# WooferAmpIR2153.net
KiCad netlist of a schematic drawn in EAGLE
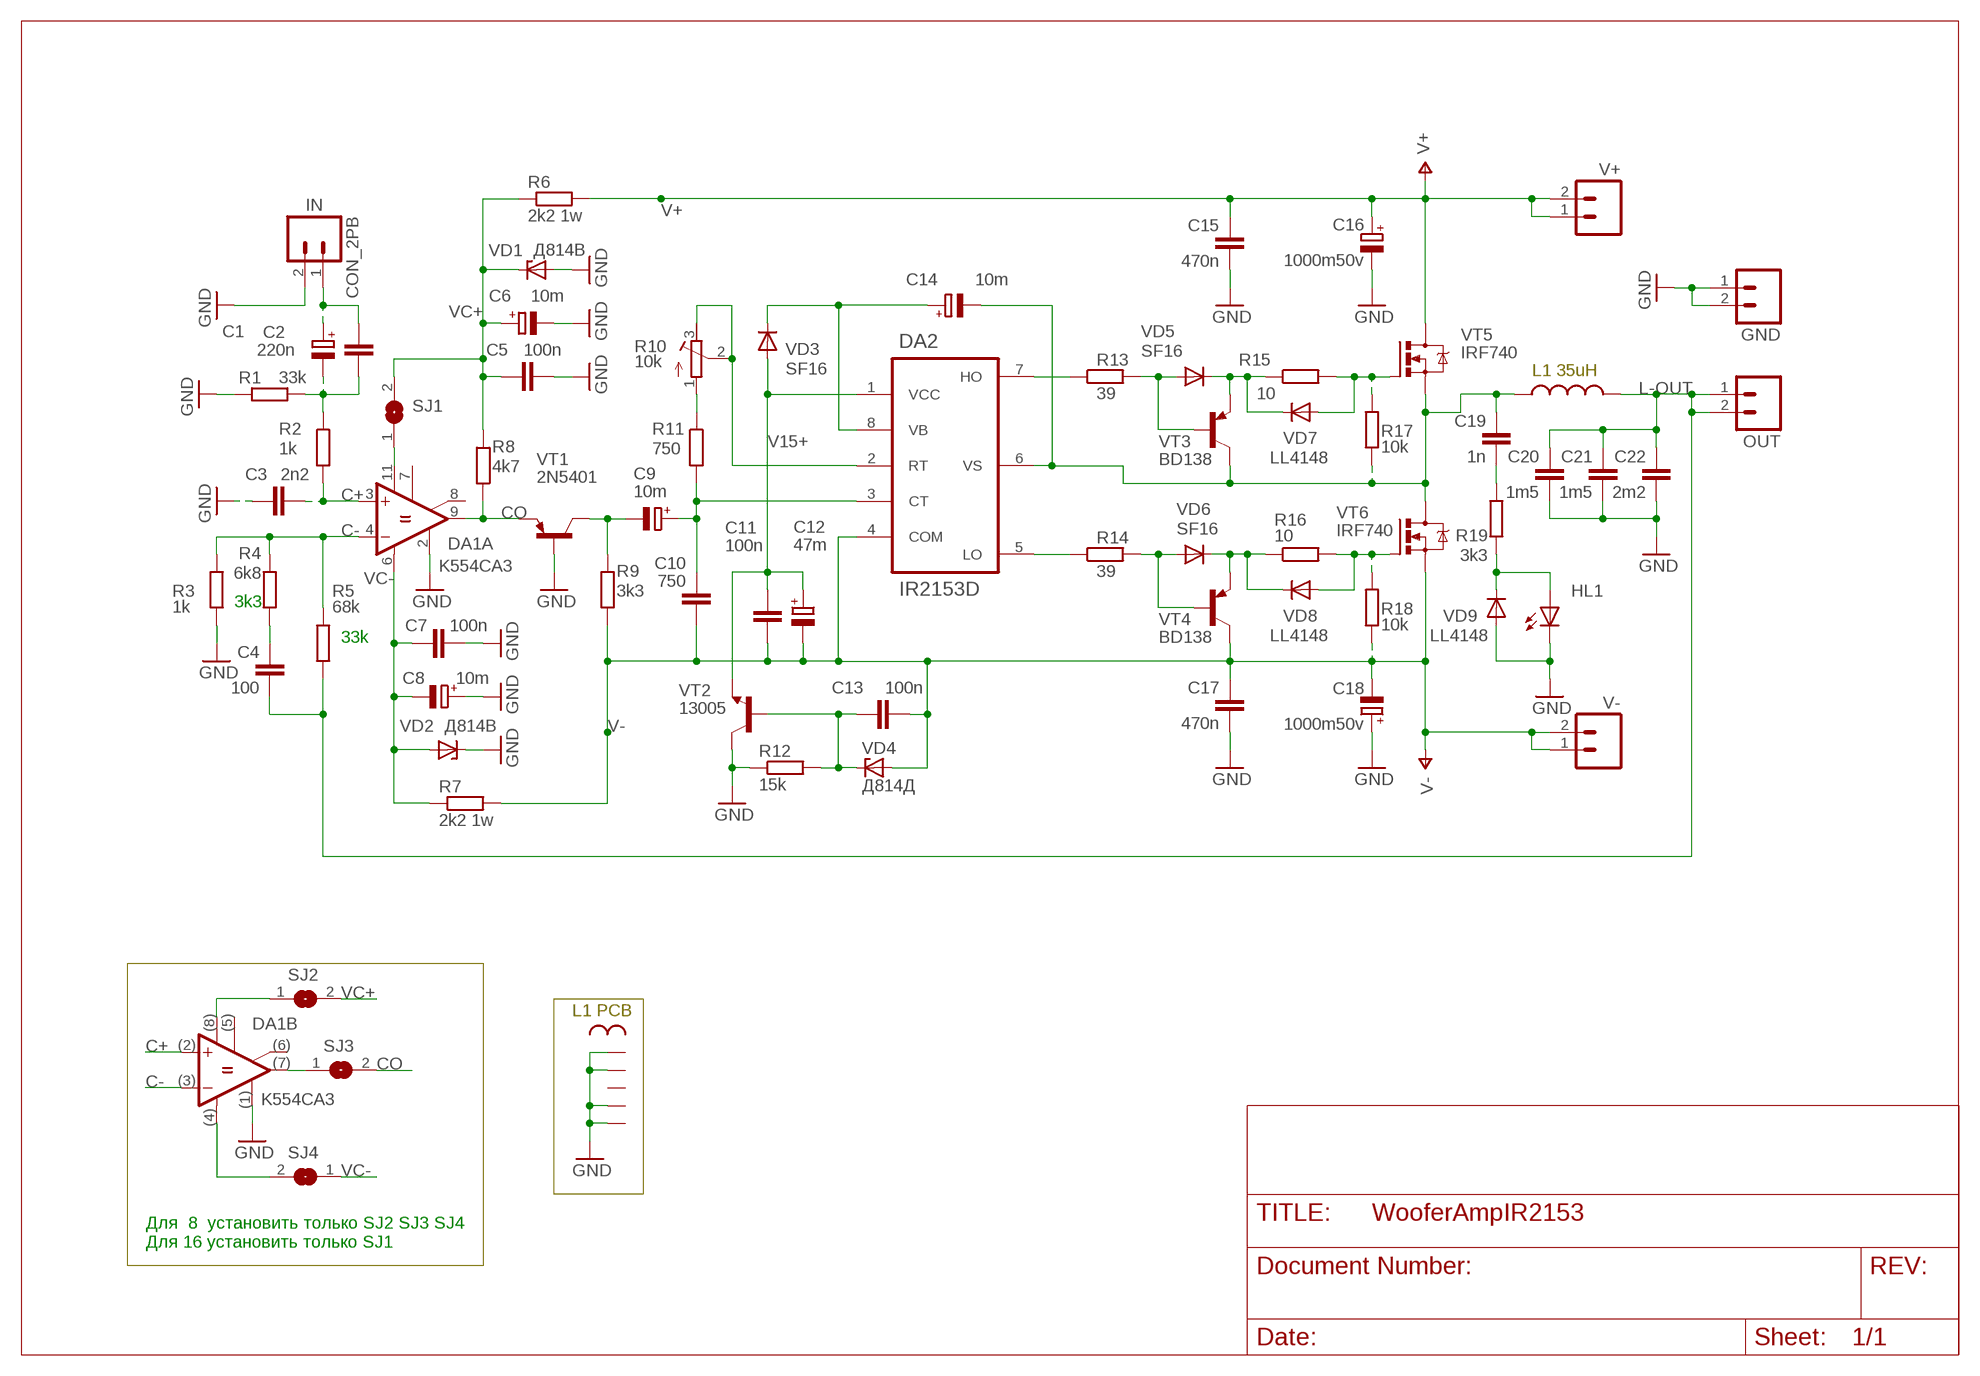
[diagram p0: schematic, sheet 1]

(export (version "E")
  (design (tool "Eeschema 10.0.6"))
  (components
    (comp (ref "C1")
      (value "CPOL-EUE2.5-6")
      (footprint "eagle-import:E2,5-6")
      (libsource (lib "eagle-import") (part "CPOL-EUE2.5-6"))
    )
    (comp (ref "C2")
      (value "220n")
      (footprint "eagle-import:C050-025X075")
      (libsource (lib "eagle-import") (part "C-EU050-025X075"))
    )
    (comp (ref "C3")
      (value "2n2")
      (footprint "eagle-import:C050-025X075")
      (libsource (lib "eagle-import") (part "C-EU050-025X075"))
    )
    (comp (ref "C4")
      (value "100")
      (footprint "eagle-import:C_11X3.5")
      (libsource (lib "eagle-import") (part "C11X3.5"))
    )
    (comp (ref "C5")
      (value "100n")
      (footprint "eagle-import:C075-032X103")
      (libsource (lib "eagle-import") (part "C-EU075-032X103"))
    )
    (comp (ref "C6")
      (value "10m")
      (footprint "eagle-import:E2,5-6")
      (libsource (lib "eagle-import") (part "CPOL-EUE2.5-6"))
    )
    (comp (ref "C7")
      (value "100n")
      (footprint "eagle-import:C050-025X075")
      (libsource (lib "eagle-import") (part "C-EU050-025X075"))
    )
    (comp (ref "C8")
      (value "10m")
      (footprint "eagle-import:E2,5-6")
      (libsource (lib "eagle-import") (part "CPOL-EUE2.5-6"))
    )
    (comp (ref "C9")
      (value "10m")
      (footprint "eagle-import:E2,5-6")
      (libsource (lib "eagle-import") (part "CPOL-EUE2.5-6"))
    )
    (comp (ref "C10")
      (value "750")
      (footprint "eagle-import:C075-032X103")
      (libsource (lib "eagle-import") (part "C-EU075-032X103"))
    )
    (comp (ref "C11")
      (value "100n")
      (footprint "eagle-import:C050-025X075")
      (libsource (lib "eagle-import") (part "C-EU050-025X075"))
    )
    (comp (ref "C12")
      (value "47m")
      (footprint "eagle-import:E2,5-6")
      (libsource (lib "eagle-import") (part "CPOL-EUE2.5-6"))
    )
    (comp (ref "C13")
      (value "100n")
      (footprint "eagle-import:C050-025X075")
      (libsource (lib "eagle-import") (part "C-EU050-025X075"))
    )
    (comp (ref "C14")
      (value "10m")
      (footprint "eagle-import:E2,5-6")
      (libsource (lib "eagle-import") (part "CPOL-EUE2.5-6"))
    )
    (comp (ref "C15")
      (value "470n")
      (footprint "eagle-import:C150-072X183")
      (libsource (lib "eagle-import") (part "C-EU150-072X183"))
    )
    (comp (ref "C16")
      (value "1000m50v")
      (footprint "eagle-import:E7,5-18")
      (libsource (lib "eagle-import") (part "CPOL-EUE7.5-18"))
    )
    (comp (ref "C17")
      (value "470n")
      (footprint "eagle-import:C150-072X183")
      (libsource (lib "eagle-import") (part "C-EU150-072X183"))
    )
    (comp (ref "C18")
      (value "1000m50v")
      (footprint "eagle-import:E7,5-18")
      (libsource (lib "eagle-import") (part "CPOL-EUE7.5-18"))
    )
    (comp (ref "C19")
      (value "1n")
      (footprint "eagle-import:C050-025X075")
      (libsource (lib "eagle-import") (part "C-EU050-025X075"))
    )
    (comp (ref "C20")
      (value "1m5")
      (footprint "eagle-import:C_22X13")
      (libsource (lib "eagle-import") (part "C22X13"))
    )
    (comp (ref "C21")
      (value "1m5")
      (footprint "eagle-import:C_22X13")
      (libsource (lib "eagle-import") (part "C22X13"))
    )
    (comp (ref "C22")
      (value "2m2")
      (footprint "eagle-import:C_23X16")
      (libsource (lib "eagle-import") (part "C23X16"))
    )
    (comp (ref "DA1")
      (value "K554CA3")
      (footprint "eagle-import:DIL_A(14)")
      (libsource (lib "eagle-import") (part "COMPMOD-K554CA3{dblquote}"))
    )
    (comp (ref "DA2")
      (value "IR2153D")
      (footprint "eagle-import:DIL8")
      (libsource (lib "eagle-import") (part "IR2153D"))
    )
    (comp (ref "GND")
      (value "CON_2PA")
      (footprint "eagle-import:CON_PWR_2PIN4MM")
      (libsource (lib "eagle-import") (part "CON_2PA"))
    )
    (comp (ref "HL1")
      (value "LED3MM")
      (footprint "eagle-import:LED3MM")
      (libsource (lib "eagle-import") (part "LED3MM"))
    )
    (comp (ref "IN")
      (value "CON_2PB")
      (footprint "eagle-import:CON_PWRI_2PIN4MM")
      (libsource (lib "eagle-import") (part "CON_2PB"))
    )
    (comp (ref "OUT")
      (value "CON_2PA")
      (footprint "eagle-import:CON_PWR_2PIN4MM")
      (libsource (lib "eagle-import") (part "CON_2PA"))
    )
    (comp (ref "R1")
      (value "33k")
      (footprint "eagle-import:0207_10")
      (libsource (lib "eagle-import") (part "R-EU_0207/10"))
    )
    (comp (ref "R2")
      (value "1k")
      (footprint "eagle-import:0207_10")
      (libsource (lib "eagle-import") (part "R-EU_0207/10"))
    )
    (comp (ref "R3")
      (value "1k")
      (footprint "eagle-import:M0805")
      (libsource (lib "eagle-import") (part "R-EU_M0805"))
    )
    (comp (ref "R4")
      (value "6k8")
      (footprint "eagle-import:M0805")
      (libsource (lib "eagle-import") (part "R-EU_M0805"))
    )
    (comp (ref "R5")
      (value "68k")
      (footprint "eagle-import:M1206")
      (libsource (lib "eagle-import") (part "R-EU_M1206"))
    )
    (comp (ref "R6")
      (value "2k2 1w")
      (footprint "eagle-import:P0613_15")
      (libsource (lib "eagle-import") (part "R-EU_0613/15"))
    )
    (comp (ref "R7")
      (value "2k2 1w")
      (footprint "eagle-import:P0613_15")
      (libsource (lib "eagle-import") (part "R-EU_0613/15"))
    )
    (comp (ref "R8")
      (value "4k7")
      (footprint "eagle-import:M0805")
      (libsource (lib "eagle-import") (part "R-EU_M0805"))
    )
    (comp (ref "R9")
      (value "3k3")
      (footprint "eagle-import:0207_10")
      (libsource (lib "eagle-import") (part "R-EU_0207/10"))
    )
    (comp (ref "R10")
      (value "10k")
      (footprint "eagle-import:RTRIM3296W")
      (libsource (lib "eagle-import") (part "R-TRIMM3296W"))
    )
    (comp (ref "R11")
      (value "750")
      (footprint "eagle-import:M0805")
      (libsource (lib "eagle-import") (part "R-EU_M0805"))
    )
    (comp (ref "R12")
      (value "15k")
      (footprint "eagle-import:0207_10")
      (libsource (lib "eagle-import") (part "R-EU_0207/10"))
    )
    (comp (ref "R13")
      (value "39")
      (footprint "eagle-import:M1206")
      (libsource (lib "eagle-import") (part "R-EU_M1206"))
    )
    (comp (ref "R14")
      (value "39")
      (footprint "eagle-import:M1206")
      (libsource (lib "eagle-import") (part "R-EU_M1206"))
    )
    (comp (ref "R15")
      (value "10")
      (footprint "eagle-import:M1206")
      (libsource (lib "eagle-import") (part "R-EU_M1206"))
    )
    (comp (ref "R16")
      (value "10")
      (footprint "eagle-import:M1206")
      (libsource (lib "eagle-import") (part "R-EU_M1206"))
    )
    (comp (ref "R17")
      (value "10k")
      (footprint "eagle-import:M1206")
      (libsource (lib "eagle-import") (part "R-EU_M1206"))
    )
    (comp (ref "R18")
      (value "10k")
      (footprint "eagle-import:M1206")
      (libsource (lib "eagle-import") (part "R-EU_M1206"))
    )
    (comp (ref "R19")
      (value "3k3")
      (footprint "eagle-import:M1206")
      (libsource (lib "eagle-import") (part "R-EU_M1206"))
    )
    (comp (ref "SJ1") (value "SJ") (footprint "eagle-import:SJ") (libsource (lib "eagle-import") (part "SJ")))
    (comp (ref "SJ2") (value "SJ") (footprint "eagle-import:SJ") (libsource (lib "eagle-import") (part "SJ")))
    (comp (ref "SJ3") (value "SJ") (footprint "eagle-import:SJ") (libsource (lib "eagle-import") (part "SJ")))
    (comp (ref "SJ4") (value "SJ") (footprint "eagle-import:SJ") (libsource (lib "eagle-import") (part "SJ")))
    (comp (ref "U$1")
      (value "L-D30")
      (footprint "eagle-import:L-D30")
      (libsource (lib "eagle-import") (part "L-D30"))
    )
    (comp (ref "U$4")
      (value "PIN")
      (footprint "eagle-import:PIN-L")
      (libsource (lib "eagle-import") (part "PIN"))
    )
    (comp (ref "U$11")
      (value "PIN")
      (footprint "eagle-import:PIN-L")
      (libsource (lib "eagle-import") (part "PIN"))
    )
    (comp (ref "V+")
      (value "CON_2PA")
      (footprint "eagle-import:CON_PWR_2PIN4MM")
      (libsource (lib "eagle-import") (part "CON_2PA"))
    )
    (comp (ref "V-")
      (value "CON_2PA")
      (footprint "eagle-import:CON_PWR_2PIN4MM")
      (libsource (lib "eagle-import") (part "CON_2PA"))
    )
    (comp (ref "VD1")
      (value "Д814В")
      (footprint "eagle-import:ZDMETAL")
      (libsource (lib "eagle-import") (part "ZDD814"))
    )
    (comp (ref "VD2")
      (value "Д814В")
      (footprint "eagle-import:ZDMETAL")
      (libsource (lib "eagle-import") (part "ZDD814"))
    )
    (comp (ref "VD3")
      (value "SF16")
      (footprint "eagle-import:DO204-10")
      (libsource (lib "eagle-import") (part "DIODE-DO204-10"))
    )
    (comp (ref "VD4")
      (value "Д814Д")
      (footprint "eagle-import:ZDMETAL")
      (libsource (lib "eagle-import") (part "ZDD814"))
    )
    (comp (ref "VD5")
      (value "SF16")
      (footprint "eagle-import:DO204-10")
      (libsource (lib "eagle-import") (part "DIODE-DO204-10"))
    )
    (comp (ref "VD6")
      (value "SF16")
      (footprint "eagle-import:DO204-10")
      (libsource (lib "eagle-import") (part "DIODE-DO204-10"))
    )
    (comp (ref "VD7")
      (value "LL4148")
      (footprint "eagle-import:SOD80C")
      (libsource (lib "eagle-import") (part "DIODE-SOD80C"))
    )
    (comp (ref "VD8")
      (value "LL4148")
      (footprint "eagle-import:SOD80C")
      (libsource (lib "eagle-import") (part "DIODE-SOD80C"))
    )
    (comp (ref "VD9")
      (value "LL4148")
      (footprint "eagle-import:SOD80C")
      (libsource (lib "eagle-import") (part "DIODE-SOD80C"))
    )
    (comp (ref "VT1")
      (value "2N5401")
      (footprint "eagle-import:TO92")
      (libsource (lib "eagle-import") (part "BJT_PNP_TO-92_EBC"))
    )
    (comp (ref "VT2")
      (value "13005")
      (footprint "eagle-import:TO220FV")
      (libsource (lib "eagle-import") (part "BJT_NPN_TO220_V_BCE"))
    )
    (comp (ref "VT3")
      (value "BD138")
      (footprint "eagle-import:TO126V")
      (libsource (lib "eagle-import") (part "BJT_PNP_TO126_V_ECB"))
    )
    (comp (ref "VT4")
      (value "BD138")
      (footprint "eagle-import:TO126V")
      (libsource (lib "eagle-import") (part "BJT_PNP_TO126_V_ECB"))
    )
    (comp (ref "VT5")
      (value "IRF740")
      (footprint "eagle-import:TO220")
      (libsource (lib "eagle-import") (part "IRF740"))
    )
    (comp (ref "VT6")
      (value "IRF740")
      (footprint "eagle-import:TO220")
      (libsource (lib "eagle-import") (part "IRF740"))
    )
  )
  (nets
    (net (code "1") (name "/C+") (class "Default")
      (node (ref "C3") (pin "2") (pinfunction "2_2") (pintype "passive"))
      (node (ref "DA1") (pin "(2)") (pinfunction "+IN_(2)") (pintype "input"))
      (node (ref "DA1") (pin "3") (pinfunction "+IN_3") (pintype "input"))
      (node (ref "R2") (pin "2") (pinfunction "2_2") (pintype "passive"))
    )
    (net (code "2") (name "/C-") (class "Default")
      (node (ref "DA1") (pin "(3)") (pinfunction "-IN_(3)") (pintype "input"))
      (node (ref "DA1") (pin "4") (pinfunction "-IN_4") (pintype "input"))
      (node (ref "R3") (pin "2") (pinfunction "2_2") (pintype "passive"))
      (node (ref "R4") (pin "2") (pinfunction "2_2") (pintype "passive"))
      (node (ref "R5") (pin "2") (pinfunction "2_2") (pintype "passive"))
    )
    (net (code "3") (name "/CO") (class "Default")
      (node (ref "DA1") (pin "9") (pinfunction "OUT_9") (pintype "output"))
      (node (ref "R8") (pin "1") (pinfunction "1_1") (pintype "passive"))
      (node (ref "SJ3") (pin "2") (pinfunction "2_2") (pintype "passive"))
      (node (ref "VT1") (pin "1") (pinfunction "E_1") (pintype "passive"))
    )
    (net (code "4") (name "/L-OUT") (class "Default")
      (node (ref "C20") (pin "1") (pinfunction "1_1") (pintype "passive"))
      (node (ref "C21") (pin "1") (pinfunction "1_1") (pintype "passive"))
      (node (ref "C22") (pin "1") (pinfunction "1_1") (pintype "passive"))
      (node (ref "C4") (pin "2") (pinfunction "2_2") (pintype "passive"))
      (node (ref "OUT") (pin "1") (pinfunction "1_1") (pintype "passive"))
      (node (ref "OUT") (pin "2") (pinfunction "2_2") (pintype "passive"))
      (node (ref "R5") (pin "1") (pinfunction "1_1") (pintype "passive"))
      (node (ref "U$11") (pin "P$1") (pinfunction "1_P$1") (pintype "bidirectional"))
    )
    (net (code "5") (name "/V15+") (class "Default")
      (node (ref "C11") (pin "1") (pinfunction "1_1") (pintype "passive"))
      (node (ref "C12") (pin "+") (pinfunction "+_+") (pintype "passive"))
      (node (ref "DA2") (pin "1") (pinfunction "VCC_1") (pintype "power_in"))
      (node (ref "VD3") (pin "A") (pinfunction "A_A") (pintype "passive"))
      (node (ref "VT2") (pin "3") (pinfunction "E_3") (pintype "passive"))
    )
    (net (code "6") (name "/VC+") (class "Default")
      (node (ref "C5") (pin "1") (pinfunction "1_1") (pintype "passive"))
      (node (ref "C6") (pin "+") (pinfunction "+_+") (pintype "passive"))
      (node (ref "R6") (pin "1") (pinfunction "1_1") (pintype "passive"))
      (node (ref "R8") (pin "2") (pinfunction "2_2") (pintype "passive"))
      (node (ref "SJ1") (pin "2") (pinfunction "2_2") (pintype "passive"))
      (node (ref "SJ2") (pin "2") (pinfunction "2_2") (pintype "passive"))
      (node (ref "VD1") (pin "C") (pinfunction "C_C") (pintype "passive"))
    )
    (net (code "7") (name "/VC-") (class "Default")
      (node (ref "C7") (pin "1") (pinfunction "1_1") (pintype "passive"))
      (node (ref "C8") (pin "-") (pinfunction "-_-") (pintype "passive"))
      (node (ref "DA1") (pin "6") (pinfunction "V-_6") (pintype "power_in"))
      (node (ref "R7") (pin "1") (pinfunction "1_1") (pintype "passive"))
      (node (ref "SJ4") (pin "1") (pinfunction "1_1") (pintype "passive"))
      (node (ref "VD2") (pin "A") (pinfunction "A_A") (pintype "passive"))
    )
    (net (code "8") (name "GND") (class "Default")
      (node (ref "C15") (pin "2") (pinfunction "2_2") (pintype "passive"))
      (node (ref "C16") (pin "-") (pinfunction "-_-") (pintype "passive"))
      (node (ref "C17") (pin "2") (pinfunction "2_2") (pintype "passive"))
      (node (ref "C18") (pin "+") (pinfunction "+_+") (pintype "passive"))
      (node (ref "C20") (pin "2") (pinfunction "2_2") (pintype "passive"))
      (node (ref "C21") (pin "2") (pinfunction "2_2") (pintype "passive"))
      (node (ref "C22") (pin "2") (pinfunction "2_2") (pintype "passive"))
      (node (ref "C3") (pin "1") (pinfunction "1_1") (pintype "passive"))
      (node (ref "C5") (pin "2") (pinfunction "2_2") (pintype "passive"))
      (node (ref "C6") (pin "-") (pinfunction "-_-") (pintype "passive"))
      (node (ref "C7") (pin "2") (pinfunction "2_2") (pintype "passive"))
      (node (ref "C8") (pin "+") (pinfunction "+_+") (pintype "passive"))
      (node (ref "DA1") (pin "(1)") (pinfunction "GND_(1)") (pintype "passive"))
      (node (ref "DA1") (pin "2") (pinfunction "GND_2") (pintype "passive"))
      (node (ref "GND") (pin "1") (pinfunction "1_1") (pintype "passive"))
      (node (ref "GND") (pin "2") (pinfunction "2_2") (pintype "passive"))
      (node (ref "HL1") (pin "K") (pinfunction "C_K") (pintype "passive"))
      (node (ref "IN") (pin "2") (pinfunction "2_2") (pintype "passive"))
      (node (ref "R1") (pin "2") (pinfunction "2_2") (pintype "passive"))
      (node (ref "R12") (pin "1") (pinfunction "1_1") (pintype "passive"))
      (node (ref "R3") (pin "1") (pinfunction "1_1") (pintype "passive"))
      (node (ref "U$1") (pin "1A") (pinfunction "1_1A") (pintype "bidirectional"))
      (node (ref "U$1") (pin "1B") (pinfunction "1_1B") (pintype "bidirectional"))
      (node (ref "U$1") (pin "2B") (pinfunction "1_2B") (pintype "bidirectional"))
      (node (ref "U$1") (pin "D") (pinfunction "1_D") (pintype "bidirectional"))
      (node (ref "VD1") (pin "A") (pinfunction "A_A") (pintype "passive"))
      (node (ref "VD2") (pin "C") (pinfunction "C_C") (pintype "passive"))
      (node (ref "VD9") (pin "A") (pinfunction "A_A") (pintype "passive"))
      (node (ref "VT1") (pin "2") (pinfunction "B_2") (pintype "passive"))
      (node (ref "VT2") (pin "2") (pinfunction "C_2") (pintype "passive"))
    )
    (net (code "9") (name "Net-(C1-Pad+)") (class "Default")
      (node (ref "C1") (pin "+") (pinfunction "+_+") (pintype "passive"))
      (node (ref "C2") (pin "1") (pinfunction "1_1") (pintype "passive"))
      (node (ref "IN") (pin "1") (pinfunction "1_1") (pintype "passive"))
    )
    (net (code "10") (name "Net-(C1-Pad-)") (class "Default")
      (node (ref "C1") (pin "-") (pinfunction "-_-") (pintype "passive"))
      (node (ref "C2") (pin "2") (pinfunction "2_2") (pintype "passive"))
      (node (ref "R1") (pin "1") (pinfunction "1_1") (pintype "passive"))
      (node (ref "R2") (pin "1") (pinfunction "1_1") (pintype "passive"))
    )
    (net (code "11") (name "Net-(C4-Pad1)") (class "Default")
      (node (ref "C4") (pin "1") (pinfunction "1_1") (pintype "passive"))
      (node (ref "R4") (pin "1") (pinfunction "1_1") (pintype "passive"))
    )
    (net (code "12") (name "Net-(C19-Pad2)") (class "Default")
      (node (ref "C19") (pin "2") (pinfunction "2_2") (pintype "passive"))
      (node (ref "R19") (pin "2") (pinfunction "2_2") (pintype "passive"))
    )
    (net (code "13") (name "Net-(DA1A-V+)") (class "Default")
      (node (ref "DA1") (pin "11") (pinfunction "V+_11") (pintype "power_in"))
      (node (ref "SJ1") (pin "1") (pinfunction "1_1") (pintype "passive"))
    )
    (net (code "14") (name "Net-(DA1B-OUT)") (class "Default")
      (node (ref "DA1") (pin "(7)") (pinfunction "OUT_(7)") (pintype "output"))
      (node (ref "SJ3") (pin "1") (pinfunction "1_1") (pintype "passive"))
    )
    (net (code "15") (name "Net-(DA1B-V+)") (class "Default")
      (node (ref "DA1") (pin "(8)") (pinfunction "V+_(8)") (pintype "power_in"))
      (node (ref "SJ2") (pin "1") (pinfunction "1_1") (pintype "passive"))
    )
    (net (code "16") (name "Net-(DA1B-V-)") (class "Default")
      (node (ref "DA1") (pin "(4)") (pinfunction "V-_(4)") (pintype "power_in"))
      (node (ref "SJ4") (pin "2") (pinfunction "2_2") (pintype "passive"))
    )
    (net (code "17") (name "Net-(DA2-CT)") (class "Default")
      (node (ref "C10") (pin "1") (pinfunction "1_1") (pintype "passive"))
      (node (ref "C9") (pin "+") (pinfunction "+_+") (pintype "passive"))
      (node (ref "DA2") (pin "3") (pinfunction "CT_3") (pintype "input"))
      (node (ref "R11") (pin "2") (pinfunction "2_2") (pintype "passive"))
    )
    (net (code "18") (name "Net-(DA2-HO)") (class "Default")
      (node (ref "DA2") (pin "7") (pinfunction "HO_7") (pintype "output"))
      (node (ref "R13") (pin "1") (pinfunction "1_1") (pintype "passive"))
    )
    (net (code "19") (name "Net-(DA2-LO)") (class "Default")
      (node (ref "DA2") (pin "5") (pinfunction "LO_5") (pintype "output"))
      (node (ref "R14") (pin "1") (pinfunction "1_1") (pintype "passive"))
    )
    (net (code "20") (name "Net-(DA2-RT)") (class "Default")
      (node (ref "DA2") (pin "2") (pinfunction "RT_2") (pintype "input"))
      (node (ref "R10") (pin "2") (pinfunction "S_2") (pintype "passive"))
      (node (ref "R10") (pin "3") (pinfunction "A_3") (pintype "passive"))
    )
    (net (code "21") (name "Net-(DA2-VB)") (class "Default")
      (node (ref "C14") (pin "+") (pinfunction "+_+") (pintype "passive"))
      (node (ref "DA2") (pin "8") (pinfunction "VB_8") (pintype "power_in"))
      (node (ref "VD3") (pin "C") (pinfunction "C_C") (pintype "passive"))
    )
    (net (code "22") (name "Net-(DA2-VS)") (class "Default")
      (node (ref "C14") (pin "-") (pinfunction "-_-") (pintype "passive"))
      (node (ref "C19") (pin "1") (pinfunction "1_1") (pintype "passive"))
      (node (ref "DA2") (pin "6") (pinfunction "VS_6") (pintype "power_in"))
      (node (ref "R17") (pin "1") (pinfunction "1_1") (pintype "passive"))
      (node (ref "U$4") (pin "P$1") (pinfunction "1_P$1") (pintype "bidirectional"))
      (node (ref "VT3") (pin "2") (pinfunction "C_2") (pintype "passive"))
      (node (ref "VT5") (pin "3") (pinfunction "S_3") (pintype "passive"))
      (node (ref "VT6") (pin "2") (pinfunction "D_2") (pintype "passive"))
    )
    (net (code "23") (name "Net-(HL1-PadA)") (class "Default")
      (node (ref "HL1") (pin "A") (pinfunction "A_A") (pintype "passive"))
      (node (ref "R19") (pin "1") (pinfunction "1_1") (pintype "passive"))
      (node (ref "VD9") (pin "C") (pinfunction "C_C") (pintype "passive"))
    )
    (net (code "24") (name "Net-(R10-E)") (class "Default")
      (node (ref "R10") (pin "1") (pinfunction "E_1") (pintype "passive"))
      (node (ref "R11") (pin "1") (pinfunction "1_1") (pintype "passive"))
    )
    (net (code "25") (name "Net-(VT1-C)") (class "Default")
      (node (ref "C9") (pin "-") (pinfunction "-_-") (pintype "passive"))
      (node (ref "R9") (pin "1") (pinfunction "1_1") (pintype "passive"))
      (node (ref "VT1") (pin "3") (pinfunction "C_3") (pintype "passive"))
    )
    (net (code "26") (name "Net-(VT2-B)") (class "Default")
      (node (ref "C13") (pin "1") (pinfunction "1_1") (pintype "passive"))
      (node (ref "R12") (pin "2") (pinfunction "2_2") (pintype "passive"))
      (node (ref "VD4") (pin "C") (pinfunction "C_C") (pintype "passive"))
      (node (ref "VT2") (pin "1") (pinfunction "B_1") (pintype "passive"))
    )
    (net (code "27") (name "Net-(VT3-B)") (class "Default")
      (node (ref "R13") (pin "2") (pinfunction "2_2") (pintype "passive"))
      (node (ref "VD5") (pin "A") (pinfunction "A_A") (pintype "passive"))
      (node (ref "VT3") (pin "3") (pinfunction "B_3") (pintype "passive"))
    )
    (net (code "28") (name "Net-(VT3-E)") (class "Default")
      (node (ref "R15") (pin "1") (pinfunction "1_1") (pintype "passive"))
      (node (ref "VD5") (pin "C") (pinfunction "C_C") (pintype "passive"))
      (node (ref "VD7") (pin "C") (pinfunction "C_C") (pintype "passive"))
      (node (ref "VT3") (pin "1") (pinfunction "E_1") (pintype "passive"))
    )
    (net (code "29") (name "Net-(VT4-B)") (class "Default")
      (node (ref "R14") (pin "2") (pinfunction "2_2") (pintype "passive"))
      (node (ref "VD6") (pin "A") (pinfunction "A_A") (pintype "passive"))
      (node (ref "VT4") (pin "3") (pinfunction "B_3") (pintype "passive"))
    )
    (net (code "30") (name "Net-(VT4-E)") (class "Default")
      (node (ref "R16") (pin "1") (pinfunction "1_1") (pintype "passive"))
      (node (ref "VD6") (pin "C") (pinfunction "C_C") (pintype "passive"))
      (node (ref "VD8") (pin "C") (pinfunction "C_C") (pintype "passive"))
      (node (ref "VT4") (pin "1") (pinfunction "E_1") (pintype "passive"))
    )
    (net (code "31") (name "Net-(VT5-G)") (class "Default")
      (node (ref "R15") (pin "2") (pinfunction "2_2") (pintype "passive"))
      (node (ref "R17") (pin "2") (pinfunction "2_2") (pintype "passive"))
      (node (ref "VD7") (pin "A") (pinfunction "A_A") (pintype "passive"))
      (node (ref "VT5") (pin "1") (pinfunction "G_1") (pintype "passive"))
    )
    (net (code "32") (name "Net-(VT6-G)") (class "Default")
      (node (ref "R16") (pin "2") (pinfunction "2_2") (pintype "passive"))
      (node (ref "R18") (pin "2") (pinfunction "2_2") (pintype "passive"))
      (node (ref "VD8") (pin "A") (pinfunction "A_A") (pintype "passive"))
      (node (ref "VT6") (pin "1") (pinfunction "G_1") (pintype "passive"))
    )
    (net (code "33") (name "V+") (class "Default")
      (node (ref "C15") (pin "1") (pinfunction "1_1") (pintype "passive"))
      (node (ref "C16") (pin "+") (pinfunction "+_+") (pintype "passive"))
      (node (ref "R6") (pin "2") (pinfunction "2_2") (pintype "passive"))
      (node (ref "V+") (pin "1") (pinfunction "1_1") (pintype "passive"))
      (node (ref "V+") (pin "2") (pinfunction "2_2") (pintype "passive"))
      (node (ref "VT5") (pin "2") (pinfunction "D_2") (pintype "passive"))
    )
    (net (code "34") (name "V-") (class "Default")
      (node (ref "C10") (pin "2") (pinfunction "2_2") (pintype "passive"))
      (node (ref "C11") (pin "2") (pinfunction "2_2") (pintype "passive"))
      (node (ref "C12") (pin "-") (pinfunction "-_-") (pintype "passive"))
      (node (ref "C13") (pin "2") (pinfunction "2_2") (pintype "passive"))
      (node (ref "C17") (pin "1") (pinfunction "1_1") (pintype "passive"))
      (node (ref "C18") (pin "-") (pinfunction "-_-") (pintype "passive"))
      (node (ref "DA2") (pin "4") (pinfunction "COM_4") (pintype "passive"))
      (node (ref "R18") (pin "1") (pinfunction "1_1") (pintype "passive"))
      (node (ref "R7") (pin "2") (pinfunction "2_2") (pintype "passive"))
      (node (ref "R9") (pin "2") (pinfunction "2_2") (pintype "passive"))
      (node (ref "V-") (pin "1") (pinfunction "1_1") (pintype "passive"))
      (node (ref "V-") (pin "2") (pinfunction "2_2") (pintype "passive"))
      (node (ref "VD4") (pin "A") (pinfunction "A_A") (pintype "passive"))
      (node (ref "VT4") (pin "2") (pinfunction "C_2") (pintype "passive"))
      (node (ref "VT6") (pin "3") (pinfunction "S_3") (pintype "passive"))
    )
    (net (code "35") (name "unconnected-(DA1A-ON-Pad7)") (class "Default")
      (node (ref "DA1") (pin "7") (pinfunction "ON_7") (pintype "passive"))
    )
    (net (code "36") (name "unconnected-(DA1A-ON{slash}STR-Pad8)") (class "Default")
      (node (ref "DA1") (pin "8") (pinfunction "ON/STR_8") (pintype "passive"))
    )
    (net (code "37") (name "unconnected-(DA1B-ON-Pad(5))") (class "Default")
      (node (ref "DA1") (pin "(5)") (pinfunction "ON_(5)") (pintype "passive"))
    )
    (net (code "38") (name "unconnected-(DA1B-ON{slash}STR-Pad(6))") (class "Default")
      (node (ref "DA1") (pin "(6)") (pinfunction "ON/STR_(6)") (pintype "passive"))
    )
    (net (code "39") (name "unconnected-(U$1D-1-Pad2A)") (class "Default")
      (node (ref "U$1") (pin "2A") (pinfunction "1_2A") (pintype "bidirectional"))
    )
  )
)
